# LDR_01.net
KiCad netlist of a schematic drawn in EAGLE
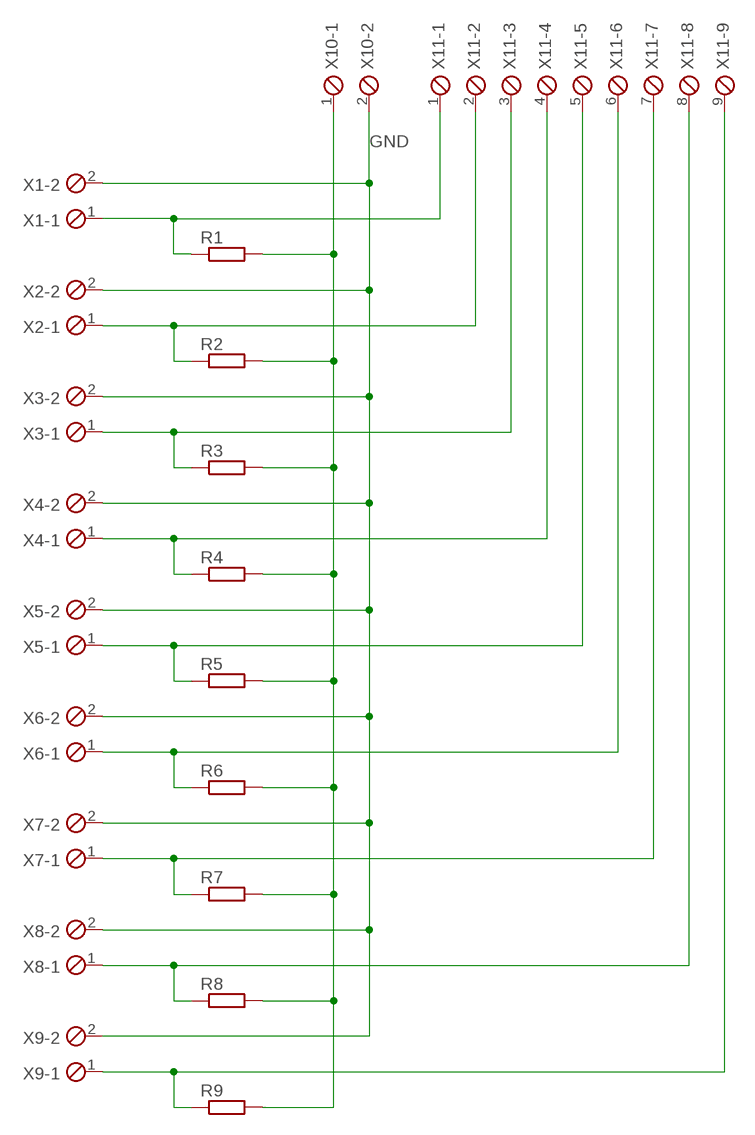
[diagram p0: schematic, sheet 1]

(export (version "E")
  (design (tool "Eeschema 10.0.6"))
  (components
    (comp (ref "R1")
      (value "R-EU_0204/7")
      (footprint "eagle-import:0204_7")
      (libsource (lib "eagle-import") (part "R-EU_0204/7"))
    )
    (comp (ref "R2")
      (value "R-EU_0204/7")
      (footprint "eagle-import:0204_7")
      (libsource (lib "eagle-import") (part "R-EU_0204/7"))
    )
    (comp (ref "R3")
      (value "R-EU_0204/7")
      (footprint "eagle-import:0204_7")
      (libsource (lib "eagle-import") (part "R-EU_0204/7"))
    )
    (comp (ref "R4")
      (value "R-EU_0204/7")
      (footprint "eagle-import:0204_7")
      (libsource (lib "eagle-import") (part "R-EU_0204/7"))
    )
    (comp (ref "R5")
      (value "R-EU_0204/7")
      (footprint "eagle-import:0204_7")
      (libsource (lib "eagle-import") (part "R-EU_0204/7"))
    )
    (comp (ref "R6")
      (value "R-EU_0204/7")
      (footprint "eagle-import:0204_7")
      (libsource (lib "eagle-import") (part "R-EU_0204/7"))
    )
    (comp (ref "R7")
      (value "R-EU_0204/7")
      (footprint "eagle-import:0204_7")
      (libsource (lib "eagle-import") (part "R-EU_0204/7"))
    )
    (comp (ref "R8")
      (value "R-EU_0204/7")
      (footprint "eagle-import:0204_7")
      (libsource (lib "eagle-import") (part "R-EU_0204/7"))
    )
    (comp (ref "R9")
      (value "R-EU_0204/7")
      (footprint "eagle-import:0204_7")
      (libsource (lib "eagle-import") (part "R-EU_0204/7"))
    )
    (comp (ref "X1")
      (value "MPT2")
      (footprint "eagle-import:2POL254")
      (libsource (lib "eagle-import") (part "MPT2"))
    )
    (comp (ref "X2")
      (value "MPT2")
      (footprint "eagle-import:2POL254")
      (libsource (lib "eagle-import") (part "MPT2"))
    )
    (comp (ref "X3")
      (value "MPT2")
      (footprint "eagle-import:2POL254")
      (libsource (lib "eagle-import") (part "MPT2"))
    )
    (comp (ref "X4")
      (value "MPT2")
      (footprint "eagle-import:2POL254")
      (libsource (lib "eagle-import") (part "MPT2"))
    )
    (comp (ref "X5")
      (value "MPT2")
      (footprint "eagle-import:2POL254")
      (libsource (lib "eagle-import") (part "MPT2"))
    )
    (comp (ref "X6")
      (value "MPT2")
      (footprint "eagle-import:2POL254")
      (libsource (lib "eagle-import") (part "MPT2"))
    )
    (comp (ref "X7")
      (value "MPT2")
      (footprint "eagle-import:2POL254")
      (libsource (lib "eagle-import") (part "MPT2"))
    )
    (comp (ref "X8")
      (value "MPT2")
      (footprint "eagle-import:2POL254")
      (libsource (lib "eagle-import") (part "MPT2"))
    )
    (comp (ref "X9")
      (value "MPT2")
      (footprint "eagle-import:2POL254")
      (libsource (lib "eagle-import") (part "MPT2"))
    )
    (comp (ref "X10")
      (value "MPT2")
      (footprint "eagle-import:2POL254")
      (libsource (lib "eagle-import") (part "MPT2"))
    )
    (comp (ref "X11")
      (value "MPT9")
      (footprint "eagle-import:9POL254")
      (libsource (lib "eagle-import") (part "MPT9"))
    )
  )
  (nets
    (net (code "1") (name "/GND") (class "Default")
      (node (ref "X1") (pin "2") (pinfunction "1_2") (pintype "passive"))
      (node (ref "X10") (pin "2") (pinfunction "1_2") (pintype "passive"))
      (node (ref "X2") (pin "2") (pinfunction "1_2") (pintype "passive"))
      (node (ref "X3") (pin "2") (pinfunction "1_2") (pintype "passive"))
      (node (ref "X4") (pin "2") (pinfunction "1_2") (pintype "passive"))
      (node (ref "X5") (pin "2") (pinfunction "1_2") (pintype "passive"))
      (node (ref "X6") (pin "2") (pinfunction "1_2") (pintype "passive"))
      (node (ref "X7") (pin "2") (pinfunction "1_2") (pintype "passive"))
      (node (ref "X8") (pin "2") (pinfunction "1_2") (pintype "passive"))
      (node (ref "X9") (pin "2") (pinfunction "1_2") (pintype "passive"))
    )
    (net (code "2") (name "Net-(R1-Pad1)") (class "Default")
      (node (ref "R1") (pin "1") (pinfunction "1_1") (pintype "passive"))
      (node (ref "X1") (pin "1") (pinfunction "1_1") (pintype "passive"))
      (node (ref "X11") (pin "1") (pinfunction "1_1") (pintype "passive"))
    )
    (net (code "3") (name "Net-(R1-Pad2)") (class "Default")
      (node (ref "R1") (pin "2") (pinfunction "2_2") (pintype "passive"))
      (node (ref "R2") (pin "2") (pinfunction "2_2") (pintype "passive"))
      (node (ref "R3") (pin "2") (pinfunction "2_2") (pintype "passive"))
      (node (ref "R4") (pin "2") (pinfunction "2_2") (pintype "passive"))
      (node (ref "R5") (pin "2") (pinfunction "2_2") (pintype "passive"))
      (node (ref "R6") (pin "2") (pinfunction "2_2") (pintype "passive"))
      (node (ref "R7") (pin "2") (pinfunction "2_2") (pintype "passive"))
      (node (ref "R8") (pin "2") (pinfunction "2_2") (pintype "passive"))
      (node (ref "R9") (pin "2") (pinfunction "2_2") (pintype "passive"))
      (node (ref "X10") (pin "1") (pinfunction "1_1") (pintype "passive"))
    )
    (net (code "4") (name "Net-(X11B-1)") (class "Default")
      (node (ref "R2") (pin "1") (pinfunction "1_1") (pintype "passive"))
      (node (ref "X11") (pin "2") (pinfunction "1_2") (pintype "passive"))
      (node (ref "X2") (pin "1") (pinfunction "1_1") (pintype "passive"))
    )
    (net (code "5") (name "Net-(X11C-1)") (class "Default")
      (node (ref "R3") (pin "1") (pinfunction "1_1") (pintype "passive"))
      (node (ref "X11") (pin "3") (pinfunction "1_3") (pintype "passive"))
      (node (ref "X3") (pin "1") (pinfunction "1_1") (pintype "passive"))
    )
    (net (code "6") (name "Net-(X11D-1)") (class "Default")
      (node (ref "R4") (pin "1") (pinfunction "1_1") (pintype "passive"))
      (node (ref "X11") (pin "4") (pinfunction "1_4") (pintype "passive"))
      (node (ref "X4") (pin "1") (pinfunction "1_1") (pintype "passive"))
    )
    (net (code "7") (name "Net-(X11E-1)") (class "Default")
      (node (ref "R5") (pin "1") (pinfunction "1_1") (pintype "passive"))
      (node (ref "X11") (pin "5") (pinfunction "1_5") (pintype "passive"))
      (node (ref "X5") (pin "1") (pinfunction "1_1") (pintype "passive"))
    )
    (net (code "8") (name "Net-(X11F-1)") (class "Default")
      (node (ref "R6") (pin "1") (pinfunction "1_1") (pintype "passive"))
      (node (ref "X11") (pin "6") (pinfunction "1_6") (pintype "passive"))
      (node (ref "X6") (pin "1") (pinfunction "1_1") (pintype "passive"))
    )
    (net (code "9") (name "Net-(X11G-1)") (class "Default")
      (node (ref "R7") (pin "1") (pinfunction "1_1") (pintype "passive"))
      (node (ref "X11") (pin "7") (pinfunction "1_7") (pintype "passive"))
      (node (ref "X7") (pin "1") (pinfunction "1_1") (pintype "passive"))
    )
    (net (code "10") (name "Net-(X11H-1)") (class "Default")
      (node (ref "R8") (pin "1") (pinfunction "1_1") (pintype "passive"))
      (node (ref "X11") (pin "8") (pinfunction "1_8") (pintype "passive"))
      (node (ref "X8") (pin "1") (pinfunction "1_1") (pintype "passive"))
    )
    (net (code "11") (name "Net-(X11I-1)") (class "Default")
      (node (ref "R9") (pin "1") (pinfunction "1_1") (pintype "passive"))
      (node (ref "X11") (pin "9") (pinfunction "1_9") (pintype "passive"))
      (node (ref "X9") (pin "1") (pinfunction "1_1") (pintype "passive"))
    )
  )
)
